# CTR_Power_Supply.net
KiCad netlist of a schematic drawn in Altium Designer
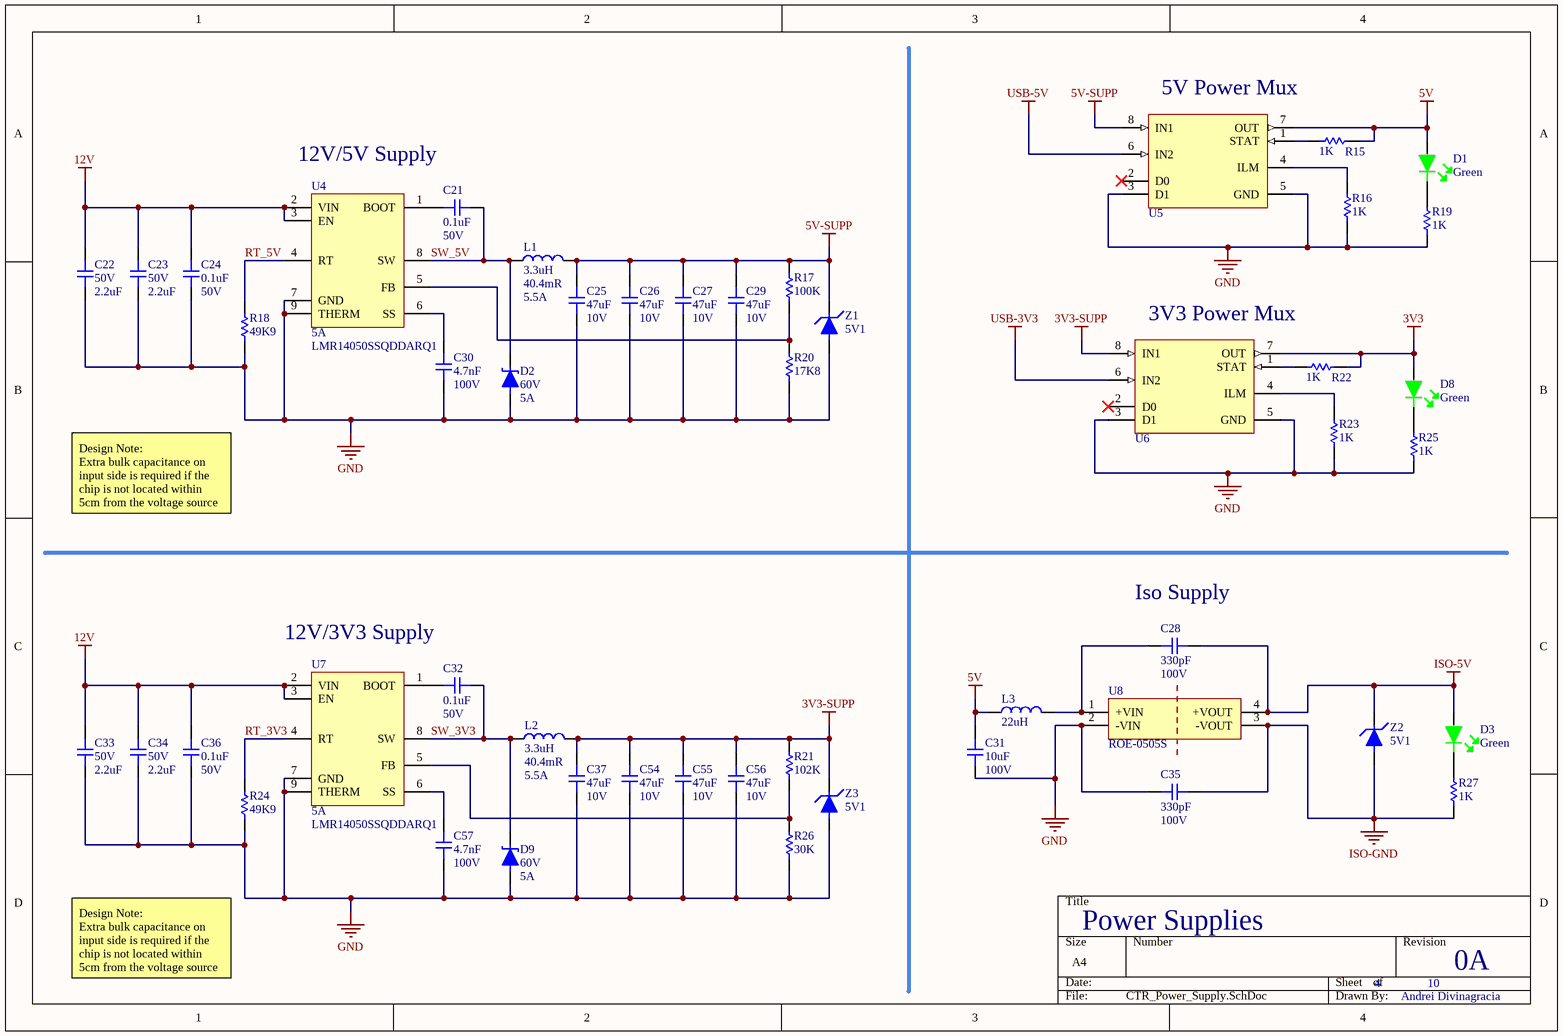
[diagram p0: CTR_Power_Supply.SchDoc]

(export (version "E")
  (design (tool "Eeschema 10.0.6"))
  (components
    (comp (ref "C21")
      (value "0.1uF")
      (footprint "CAP-0603")
      (description "CAP CER 0.1UF 50V X7R 0603")
      (fields
        (field (name "MANUFACTURER") "Samsung")
        (field (name "MANUFACTURER PART NUMBER") "CL10B104KB8NNNL")
        (field (name "VOLTAGE RATING") "50V")
      )
      (libsource (lib "InverterSCHLib") (part "0603-0.1uF-50V"))
    )
    (comp (ref "C22")
      (value "0805-2.2uF-50V")
      (footprint "CAP-0805")
      (description "CAP CER 2.2UF 50V X5R 0805")
      (fields
        (field (name "MANUFACTURER") "Samsung")
        (field (name "MANUFACTURER PART NUMBER") "CL21A225KBFNNNE")
        (field (name "VOLTAGE RATING") "50V")
        (field (name "CAPACITANCE") "2.2uF")
      )
      (libsource (lib "InverterSCHLib") (part "0805-2.2uF-50V"))
    )
    (comp (ref "C23")
      (value "0805-2.2uF-50V")
      (footprint "CAP-0805")
      (description "CAP CER 2.2UF 50V X5R 0805")
      (fields
        (field (name "MANUFACTURER") "Samsung")
        (field (name "MANUFACTURER PART NUMBER") "CL21A225KBFNNNE")
        (field (name "VOLTAGE RATING") "50V")
        (field (name "CAPACITANCE") "2.2uF")
      )
      (libsource (lib "InverterSCHLib") (part "0805-2.2uF-50V"))
    )
    (comp (ref "C24")
      (value "0.1uF")
      (footprint "CAP-0603")
      (description "CAP CER 0.1UF 50V X7R 0603")
      (fields
        (field (name "MANUFACTURER") "Samsung")
        (field (name "MANUFACTURER PART NUMBER") "CL10B104KB8NNNL")
        (field (name "VOLTAGE RATING") "50V")
      )
      (libsource (lib "InverterSCHLib") (part "0603-0.1uF-50V"))
    )
    (comp (ref "C25")
      (value "47uF")
      (footprint "CAP-1206")
      (description "CAP CER 47UF 10V X5R 1206")
      (fields
        (field (name "MANUFACTURER") "Samsung")
        (field (name "MANUFACTURER PART NUMBER") "CL31A476MPHNNNE")
        (field (name "VOLTAGE RATING") "10V")
      )
      (libsource (lib "InverterSCHLib") (part "1206-47uF"))
    )
    (comp (ref "C26")
      (value "47uF")
      (footprint "CAP-1206")
      (description "CAP CER 47UF 10V X5R 1206")
      (fields
        (field (name "MANUFACTURER") "Samsung")
        (field (name "MANUFACTURER PART NUMBER") "CL31A476MPHNNNE")
        (field (name "VOLTAGE RATING") "10V")
      )
      (libsource (lib "InverterSCHLib") (part "1206-47uF"))
    )
    (comp (ref "C27")
      (value "47uF")
      (footprint "CAP-1206")
      (description "CAP CER 47UF 10V X5R 1206")
      (fields
        (field (name "MANUFACTURER") "Samsung")
        (field (name "MANUFACTURER PART NUMBER") "CL31A476MPHNNNE")
        (field (name "VOLTAGE RATING") "10V")
      )
      (libsource (lib "InverterSCHLib") (part "1206-47uF"))
    )
    (comp (ref "C28")
      (value "330pF")
      (footprint "CAP-0805")
      (description "CAP CER 330PF 100V X7R 0805")
      (fields
        (field (name "MANUFACTURER") "Wurth Electronics")
        (field (name "MANUFACTURER PART NUMBER") "885012207113")
        (field (name "VOLTAGE RATING") "100V")
      )
      (libsource (lib "InverterSCHLib") (part "0805-330pF-100V"))
    )
    (comp (ref "C29")
      (value "47uF")
      (footprint "CAP-1206")
      (description "CAP CER 47UF 10V X5R 1206")
      (fields
        (field (name "MANUFACTURER") "Samsung")
        (field (name "MANUFACTURER PART NUMBER") "CL31A476MPHNNNE")
        (field (name "VOLTAGE RATING") "10V")
      )
      (libsource (lib "InverterSCHLib") (part "1206-47uF"))
    )
    (comp (ref "C30")
      (value "4.7nF")
      (footprint "CAP-0603")
      (description "CAP CER 4700PF 100V X7R 0603")
      (fields
        (field (name "MANUFACTURER") "TDK")
        (field (name "MANUFACTURER PART NUMBER") "CGA3E2X7R2A472K080AA")
        (field (name "VOLTAGE RATING") "100V")
      )
      (libsource (lib "InverterSCHLib") (part "0603-4.7nF-100V"))
    )
    (comp (ref "C31")
      (value "10uF")
      (description "CAP CER 10UF 100V X7S 2220")
      (fields
        (field (name "MANUFACTURER") "TDK")
        (field (name "MANUFACTURER PART NUMBER") "C5750X7S2A106K230KB")
        (field (name "VOLTAGE RATING") "100V")
      )
      (libsource (lib "InverterSCHLib") (part "2220-10uF-100V"))
    )
    (comp (ref "C32")
      (value "0.1uF")
      (footprint "CAP-0603")
      (description "CAP CER 0.1UF 50V X7R 0603")
      (fields
        (field (name "MANUFACTURER") "Samsung")
        (field (name "MANUFACTURER PART NUMBER") "CL10B104KB8NNNL")
        (field (name "VOLTAGE RATING") "50V")
      )
      (libsource (lib "InverterSCHLib") (part "0603-0.1uF-50V"))
    )
    (comp (ref "C33")
      (value "0805-2.2uF-50V")
      (footprint "CAP-0805")
      (description "CAP CER 2.2UF 50V X5R 0805")
      (fields
        (field (name "MANUFACTURER") "Samsung")
        (field (name "MANUFACTURER PART NUMBER") "CL21A225KBFNNNE")
        (field (name "VOLTAGE RATING") "50V")
        (field (name "CAPACITANCE") "2.2uF")
      )
      (libsource (lib "InverterSCHLib") (part "0805-2.2uF-50V"))
    )
    (comp (ref "C34")
      (value "0805-2.2uF-50V")
      (footprint "CAP-0805")
      (description "CAP CER 2.2UF 50V X5R 0805")
      (fields
        (field (name "MANUFACTURER") "Samsung")
        (field (name "MANUFACTURER PART NUMBER") "CL21A225KBFNNNE")
        (field (name "VOLTAGE RATING") "50V")
        (field (name "CAPACITANCE") "2.2uF")
      )
      (libsource (lib "InverterSCHLib") (part "0805-2.2uF-50V"))
    )
    (comp (ref "C35")
      (value "330pF")
      (footprint "CAP-0805")
      (description "CAP CER 330PF 100V X7R 0805")
      (fields
        (field (name "MANUFACTURER") "Wurth Electronics")
        (field (name "MANUFACTURER PART NUMBER") "885012207113")
        (field (name "VOLTAGE RATING") "100V")
      )
      (libsource (lib "InverterSCHLib") (part "0805-330pF-100V"))
    )
    (comp (ref "C36")
      (value "0.1uF")
      (footprint "CAP-0603")
      (description "CAP CER 0.1UF 50V X7R 0603")
      (fields
        (field (name "MANUFACTURER") "Samsung")
        (field (name "MANUFACTURER PART NUMBER") "CL10B104KB8NNNL")
        (field (name "VOLTAGE RATING") "50V")
      )
      (libsource (lib "InverterSCHLib") (part "0603-0.1uF-50V"))
    )
    (comp (ref "C37")
      (value "47uF")
      (footprint "CAP-1206")
      (description "CAP CER 47UF 10V X5R 1206")
      (fields
        (field (name "MANUFACTURER") "Samsung")
        (field (name "MANUFACTURER PART NUMBER") "CL31A476MPHNNNE")
        (field (name "VOLTAGE RATING") "10V")
      )
      (libsource (lib "InverterSCHLib") (part "1206-47uF"))
    )
    (comp (ref "C54")
      (value "47uF")
      (footprint "CAP-1206")
      (description "CAP CER 47UF 10V X5R 1206")
      (fields
        (field (name "MANUFACTURER") "Samsung")
        (field (name "MANUFACTURER PART NUMBER") "CL31A476MPHNNNE")
        (field (name "VOLTAGE RATING") "10V")
      )
      (libsource (lib "InverterSCHLib") (part "1206-47uF"))
    )
    (comp (ref "C55")
      (value "47uF")
      (footprint "CAP-1206")
      (description "CAP CER 47UF 10V X5R 1206")
      (fields
        (field (name "MANUFACTURER") "Samsung")
        (field (name "MANUFACTURER PART NUMBER") "CL31A476MPHNNNE")
        (field (name "VOLTAGE RATING") "10V")
      )
      (libsource (lib "InverterSCHLib") (part "1206-47uF"))
    )
    (comp (ref "C56")
      (value "47uF")
      (footprint "CAP-1206")
      (description "CAP CER 47UF 10V X5R 1206")
      (fields
        (field (name "MANUFACTURER") "Samsung")
        (field (name "MANUFACTURER PART NUMBER") "CL31A476MPHNNNE")
        (field (name "VOLTAGE RATING") "10V")
      )
      (libsource (lib "InverterSCHLib") (part "1206-47uF"))
    )
    (comp (ref "C57")
      (value "4.7nF")
      (footprint "CAP-0603")
      (description "CAP CER 4700PF 100V X7R 0603")
      (fields
        (field (name "MANUFACTURER") "TDK")
        (field (name "MANUFACTURER PART NUMBER") "CGA3E2X7R2A472K080AA")
        (field (name "VOLTAGE RATING") "100V")
      )
      (libsource (lib "InverterSCHLib") (part "0603-4.7nF-100V"))
    )
    (comp (ref "D1")
      (value "Green")
      (footprint "LED-0603")
      (description "LED GREEN CLEAR 0603 SMD")
      (fields
        (field (name "MANUFACTURER") "Wurth Electronics")
        (field (name "MANUFACTURER PART NUMBER") "150060VS75000")
      )
      (libsource (lib "InverterSCHLib") (part "LED-Green"))
    )
    (comp (ref "D2")
      (value "B560C-13-F")
      (footprint "DO-214AB, SMC")
      (description "DIODE SCHOTTKY 60V 5A SMC")
      (fields
        (field (name "MANUFACTURER") "Diodes")
        (field (name "VOLTAGE RATING (DC)") "60V")
        (field (name "CURRENT RATING") "5A")
      )
      (libsource (lib "InverterSCHLib") (part "B560C-13-F"))
    )
    (comp (ref "D3")
      (value "Green")
      (footprint "LED-0603")
      (description "LED GREEN CLEAR 0603 SMD")
      (fields
        (field (name "MANUFACTURER") "Wurth Electronics")
        (field (name "MANUFACTURER PART NUMBER") "150060VS75000")
      )
      (libsource (lib "InverterSCHLib") (part "LED-Green"))
    )
    (comp (ref "D8")
      (value "Green")
      (footprint "LED-0603")
      (description "LED GREEN CLEAR 0603 SMD")
      (fields
        (field (name "MANUFACTURER") "Wurth Electronics")
        (field (name "MANUFACTURER PART NUMBER") "150060VS75000")
      )
      (libsource (lib "InverterSCHLib") (part "LED-Green"))
    )
    (comp (ref "D9")
      (value "B560C-13-F")
      (footprint "DO-214AB, SMC")
      (description "DIODE SCHOTTKY 60V 5A SMC")
      (fields
        (field (name "MANUFACTURER") "Diodes")
        (field (name "VOLTAGE RATING (DC)") "60V")
        (field (name "CURRENT RATING") "5A")
      )
      (libsource (lib "InverterSCHLib") (part "B560C-13-F"))
    )
    (comp (ref "L1")
      (value "IND-3.3uH-5.5A")
      (footprint "INDM5252X30N")
      (description "FIXED IND 3.3UH 5.5A 40.4MOHM SM")
      (fields
        (field (name "MANUFACTURER") "Vishay Dale")
        (field (name "MANUFACTURER PART NUMBER") "IHLP2020CZER3R3M11")
        (field (name "INDUCTANCE") "3.3uH")
        (field (name "DC RESISTANCE (DCR)") "40.4mR")
        (field (name "CURRENT RATING") "5.5A")
      )
      (libsource (lib "InverterSCHLib") (part "IND-3.3uH-5.5A"))
    )
    (comp (ref "L2")
      (value "IND-3.3uH-5.5A")
      (footprint "INDM5252X30N")
      (description "FIXED IND 3.3UH 5.5A 40.4MOHM SM")
      (fields
        (field (name "MANUFACTURER") "Vishay Dale")
        (field (name "MANUFACTURER PART NUMBER") "IHLP2020CZER3R3M11")
        (field (name "INDUCTANCE") "3.3uH")
        (field (name "DC RESISTANCE (DCR)") "40.4mR")
        (field (name "CURRENT RATING") "5.5A")
      )
      (libsource (lib "InverterSCHLib") (part "IND-3.3uH-5.5A"))
    )
    (comp (ref "L3")
      (value "22uH")
      (footprint "IND-4532")
      (description "FIXED IND 22UH 630MA 700MOHM SMD")
      (fields (field (name "MANUFACTURER") "Recom") (field (name "MANUFACTURER PART NUMBER") "RLS-226"))
      (libsource (lib "InverterSCHLib") (part "IND-22uH-630mA"))
    )
    (comp (ref "R15")
      (value "1K")
      (footprint "RES-0603")
      (description "RES SMD 1K OHM 1% 1/10W 0603")
      (fields
        (field (name "MANUFACTURER") "Vishay Dale")
        (field (name "MANUFACTURER PART NUMBER") "CRCW06031K00FKEA")
      )
      (libsource (lib "InverterSCHLib") (part "0603-1KR"))
    )
    (comp (ref "R16")
      (value "1K")
      (footprint "RES-0603")
      (description "RES SMD 1K OHM 1% 1/10W 0603")
      (fields
        (field (name "MANUFACTURER") "Vishay Dale")
        (field (name "MANUFACTURER PART NUMBER") "CRCW06031K00FKEA")
      )
      (libsource (lib "InverterSCHLib") (part "0603-1KR"))
    )
    (comp (ref "R17")
      (value "100K")
      (description "RES SMD 100K OHM 1% 1/10W 0603")
      (fields
        (field (name "MANUFACTURER") "Yageo")
        (field (name "MANUFACTURER PART NUMBER") "RC0603FR-07100KL")
      )
      (libsource (lib "InverterSCHLib") (part "0603-100K"))
    )
    (comp (ref "R18")
      (value "49K9")
      (footprint "RES-0603")
      (description "RES SMD 49.9KOHM 0.5% 1/10W 0603")
      (fields
        (field (name "MANUFACTURER") "Vishay Dale")
        (field (name "MANUFACTURER PART NUMBER") "CRCW060349K9DHEAP")
      )
      (libsource (lib "InverterSCHLib") (part "0603-49K9"))
    )
    (comp (ref "R19")
      (value "1K")
      (footprint "RES-0603")
      (description "RES SMD 1K OHM 1% 1/10W 0603")
      (fields
        (field (name "MANUFACTURER") "Vishay Dale")
        (field (name "MANUFACTURER PART NUMBER") "CRCW06031K00FKEA")
      )
      (libsource (lib "InverterSCHLib") (part "0603-1KR"))
    )
    (comp (ref "R20")
      (value "17K8")
      (footprint "RES-0603")
      (description "RES SMD 17.8K OHM 1% 1/10W 0603")
      (fields
        (field (name "MANUFACTURER") "Yageo")
        (field (name "MANUFACTURER PART NUMBER") "RC0603FR-0717K8L")
      )
      (libsource (lib "InverterSCHLib") (part "0603-17K8"))
    )
    (comp (ref "R21")
      (value "102K")
      (footprint "RES-0603")
      (description "RES SMD 102K OHM 1% 1/10W 0603")
      (fields
        (field (name "MANUFACTURER") "Samsung")
        (field (name "MANUFACTURER PART NUMBER") "RC1608F1023CS")
      )
      (libsource (lib "InverterSCHLib") (part "0603-102K"))
    )
    (comp (ref "R22")
      (value "1K")
      (footprint "RES-0603")
      (description "RES SMD 1K OHM 1% 1/10W 0603")
      (fields
        (field (name "MANUFACTURER") "Vishay Dale")
        (field (name "MANUFACTURER PART NUMBER") "CRCW06031K00FKEA")
      )
      (libsource (lib "InverterSCHLib") (part "0603-1KR"))
    )
    (comp (ref "R23")
      (value "1K")
      (footprint "RES-0603")
      (description "RES SMD 1K OHM 1% 1/10W 0603")
      (fields
        (field (name "MANUFACTURER") "Vishay Dale")
        (field (name "MANUFACTURER PART NUMBER") "CRCW06031K00FKEA")
      )
      (libsource (lib "InverterSCHLib") (part "0603-1KR"))
    )
    (comp (ref "R24")
      (value "49K9")
      (footprint "RES-0603")
      (description "RES SMD 49.9KOHM 0.5% 1/10W 0603")
      (fields
        (field (name "MANUFACTURER") "Vishay Dale")
        (field (name "MANUFACTURER PART NUMBER") "CRCW060349K9DHEAP")
      )
      (libsource (lib "InverterSCHLib") (part "0603-49K9"))
    )
    (comp (ref "R25")
      (value "1K")
      (footprint "RES-0603")
      (description "RES SMD 1K OHM 1% 1/10W 0603")
      (fields
        (field (name "MANUFACTURER") "Vishay Dale")
        (field (name "MANUFACTURER PART NUMBER") "CRCW06031K00FKEA")
      )
      (libsource (lib "InverterSCHLib") (part "0603-1KR"))
    )
    (comp (ref "R26")
      (value "30K")
      (footprint "RES-0603")
      (description "RES SMD 30K OHM 1% 1/10W 0603")
      (fields
        (field (name "MANUFACTURER") "Yageo")
        (field (name "MANUFACTURER PART NUMBER") "RC0603FR-0730KL")
      )
      (libsource (lib "InverterSCHLib") (part "0603-30KR"))
    )
    (comp (ref "R27")
      (value "1K")
      (footprint "RES-0603")
      (description "RES SMD 1K OHM 1% 1/10W 0603")
      (fields
        (field (name "MANUFACTURER") "Vishay Dale")
        (field (name "MANUFACTURER PART NUMBER") "CRCW06031K00FKEA")
      )
      (libsource (lib "InverterSCHLib") (part "0603-1KR"))
    )
    (comp (ref "U4")
      (value "LMR14050SSQDDARQ1")
      (footprint "8-SOIC W THRM")
      (description "IC REG BUCK ADJUSTABLE 5A 8SOPWR")
      (fields
        (field (name "MANUFACTURER") "Texas Instruments")
        (field (name "OUTPUT CURRENT") "5A")
        (field (name "MANUFACTURER PART NUMBER") "LMR14050SSQDDARQ1")
      )
      (libsource (lib "InverterSCHLib") (part "LMR14050SSQDDARQ1"))
    )
    (comp (ref "U5")
      (value "TPS2115APWR")
      (footprint "8-TSSOP-POW-SW")
      (description "IC OR CTRLR SRC SELECT 8TSSOP")
      (fields (field (name "MANUFACTURER") "Texas Instruments"))
      (libsource (lib "InverterSCHLib") (part "TPS2115APWR"))
    )
    (comp (ref "U6")
      (value "TPS2115APWR")
      (footprint "8-TSSOP-POW-SW")
      (description "IC OR CTRLR SRC SELECT 8TSSOP")
      (fields (field (name "MANUFACTURER") "Texas Instruments"))
      (libsource (lib "InverterSCHLib") (part "TPS2115APWR"))
    )
    (comp (ref "U7")
      (value "LMR14050SSQDDARQ1")
      (footprint "8-SOIC W THRM")
      (description "IC REG BUCK ADJUSTABLE 5A 8SOPWR")
      (fields
        (field (name "MANUFACTURER") "Texas Instruments")
        (field (name "OUTPUT CURRENT") "5A")
        (field (name "MANUFACTURER PART NUMBER") "LMR14050SSQDDARQ1")
      )
      (libsource (lib "InverterSCHLib") (part "LMR14050SSQDDARQ1"))
    )
    (comp (ref "U8")
      (value "ROE-0505S")
      (footprint "ROE-0505S")
      (description "Module DC-DC 5VIN 1-OUT 5V 0.2A 1W 4-Pin SIP Tube")
      (fields (field (name "MANUFACTURER") "Recom") (field (name "MANUFACTURER PART NUMBER") "ROE-0505S"))
      (libsource (lib "InverterSCHLib") (part "ROE-0505S"))
    )
    (comp (ref "Z1")
      (value "5V1")
      (footprint "SOD-123")
      (description "DIODE ZENER 5.1V 500MW SOD123")
      (fields
        (field (name "MANUFACTURER") "ON Semiconductor")
        (field (name "MANUFACTURER PART NUMBER") "SZMMSZ4689T1G")
      )
      (libsource (lib "InverterSCHLib") (part "SZMMSZ4689T1G"))
    )
    (comp (ref "Z2")
      (value "5V1")
      (footprint "SOD-123")
      (description "DIODE ZENER 5.1V 500MW SOD123")
      (fields
        (field (name "MANUFACTURER") "ON Semiconductor")
        (field (name "MANUFACTURER PART NUMBER") "SZMMSZ4689T1G")
      )
      (libsource (lib "InverterSCHLib") (part "SZMMSZ4689T1G"))
    )
    (comp (ref "Z3")
      (value "5V1")
      (footprint "SOD-123")
      (description "DIODE ZENER 5.1V 500MW SOD123")
      (fields
        (field (name "MANUFACTURER") "ON Semiconductor")
        (field (name "MANUFACTURER PART NUMBER") "SZMMSZ4689T1G")
      )
      (libsource (lib "InverterSCHLib") (part "SZMMSZ4689T1G"))
    )
  )
  (nets
    (net (code "1") (name "/RT_3V3") (class "Default")
      (node (ref "R24") (pin "2") (pinfunction "2_2") (pintype "passive"))
      (node (ref "U7") (pin "4") (pinfunction "RT_4") (pintype "passive"))
    )
    (net (code "2") (name "/RT_5V") (class "Default")
      (node (ref "R18") (pin "2") (pinfunction "2_2") (pintype "passive"))
      (node (ref "U4") (pin "4") (pinfunction "RT_4") (pintype "passive"))
    )
    (net (code "3") (name "/SW_3V3") (class "Default")
      (node (ref "C32") (pin "1") (pinfunction "1_1") (pintype "passive"))
      (node (ref "D9") (pin "1") (pinfunction "1_1") (pintype "passive"))
      (node (ref "L2") (pin "1") (pinfunction "1_1") (pintype "passive"))
      (node (ref "U7") (pin "8") (pinfunction "SW_8") (pintype "passive"))
    )
    (net (code "4") (name "/SW_5V") (class "Default")
      (node (ref "C21") (pin "1") (pinfunction "1_1") (pintype "passive"))
      (node (ref "D2") (pin "1") (pinfunction "1_1") (pintype "passive"))
      (node (ref "L1") (pin "1") (pinfunction "1_1") (pintype "passive"))
      (node (ref "U4") (pin "8") (pinfunction "SW_8") (pintype "passive"))
    )
    (net (code "5") (name "3V3") (class "Default")
      (node (ref "D8") (pin "1") (pinfunction "1_1") (pintype "passive"))
      (node (ref "R22") (pin "2") (pinfunction "2_2") (pintype "passive"))
      (node (ref "U6") (pin "7") (pinfunction "OUT_7") (pintype "output"))
    )
    (net (code "6") (name "3V3-SUPP") (class "Default")
      (node (ref "C37") (pin "2") (pinfunction "2_2") (pintype "passive"))
      (node (ref "C54") (pin "2") (pinfunction "2_2") (pintype "passive"))
      (node (ref "C55") (pin "2") (pinfunction "2_2") (pintype "passive"))
      (node (ref "C56") (pin "2") (pinfunction "2_2") (pintype "passive"))
      (node (ref "L2") (pin "2") (pinfunction "2_2") (pintype "passive"))
      (node (ref "R21") (pin "2") (pinfunction "2_2") (pintype "passive"))
      (node (ref "U6") (pin "8") (pinfunction "IN1_8") (pintype "input"))
      (node (ref "Z3") (pin "1") (pinfunction "1_1") (pintype "passive"))
    )
    (net (code "7") (name "5V") (class "Default")
      (node (ref "C31") (pin "2") (pinfunction "2_2") (pintype "passive"))
      (node (ref "D1") (pin "1") (pinfunction "1_1") (pintype "passive"))
      (node (ref "L3") (pin "1") (pinfunction "1_1") (pintype "passive"))
      (node (ref "R15") (pin "2") (pinfunction "2_2") (pintype "passive"))
      (node (ref "U5") (pin "7") (pinfunction "OUT_7") (pintype "output"))
    )
    (net (code "8") (name "5V-SUPP") (class "Default")
      (node (ref "C25") (pin "2") (pinfunction "2_2") (pintype "passive"))
      (node (ref "C26") (pin "2") (pinfunction "2_2") (pintype "passive"))
      (node (ref "C27") (pin "2") (pinfunction "2_2") (pintype "passive"))
      (node (ref "C29") (pin "2") (pinfunction "2_2") (pintype "passive"))
      (node (ref "L1") (pin "2") (pinfunction "2_2") (pintype "passive"))
      (node (ref "R17") (pin "1") (pinfunction "1_1") (pintype "passive"))
      (node (ref "U5") (pin "8") (pinfunction "IN1_8") (pintype "input"))
      (node (ref "Z1") (pin "1") (pinfunction "1_1") (pintype "passive"))
    )
    (net (code "9") (name "12V") (class "Default")
      (node (ref "C22") (pin "1") (pinfunction "1_1") (pintype "passive"))
      (node (ref "C23") (pin "1") (pinfunction "1_1") (pintype "passive"))
      (node (ref "C24") (pin "2") (pinfunction "2_2") (pintype "passive"))
      (node (ref "C33") (pin "1") (pinfunction "1_1") (pintype "passive"))
      (node (ref "C34") (pin "1") (pinfunction "1_1") (pintype "passive"))
      (node (ref "C36") (pin "2") (pinfunction "2_2") (pintype "passive"))
      (node (ref "U4") (pin "2") (pinfunction "VIN_2") (pintype "passive"))
      (node (ref "U4") (pin "3") (pinfunction "EN_3") (pintype "passive"))
      (node (ref "U7") (pin "2") (pinfunction "VIN_2") (pintype "passive"))
      (node (ref "U7") (pin "3") (pinfunction "EN_3") (pintype "passive"))
    )
    (net (code "10") (name "GND") (class "Default")
      (node (ref "C22") (pin "2") (pinfunction "2_2") (pintype "passive"))
      (node (ref "C23") (pin "2") (pinfunction "2_2") (pintype "passive"))
      (node (ref "C24") (pin "1") (pinfunction "1_1") (pintype "passive"))
      (node (ref "C25") (pin "1") (pinfunction "1_1") (pintype "passive"))
      (node (ref "C26") (pin "1") (pinfunction "1_1") (pintype "passive"))
      (node (ref "C27") (pin "1") (pinfunction "1_1") (pintype "passive"))
      (node (ref "C29") (pin "1") (pinfunction "1_1") (pintype "passive"))
      (node (ref "C30") (pin "1") (pinfunction "1_1") (pintype "passive"))
      (node (ref "C31") (pin "1") (pinfunction "1_1") (pintype "passive"))
      (node (ref "C33") (pin "2") (pinfunction "2_2") (pintype "passive"))
      (node (ref "C34") (pin "2") (pinfunction "2_2") (pintype "passive"))
      (node (ref "C35") (pin "1") (pinfunction "1_1") (pintype "passive"))
      (node (ref "C36") (pin "1") (pinfunction "1_1") (pintype "passive"))
      (node (ref "C37") (pin "1") (pinfunction "1_1") (pintype "passive"))
      (node (ref "C54") (pin "1") (pinfunction "1_1") (pintype "passive"))
      (node (ref "C55") (pin "1") (pinfunction "1_1") (pintype "passive"))
      (node (ref "C56") (pin "1") (pinfunction "1_1") (pintype "passive"))
      (node (ref "C57") (pin "1") (pinfunction "1_1") (pintype "passive"))
      (node (ref "D2") (pin "2") (pinfunction "2_2") (pintype "passive"))
      (node (ref "D9") (pin "2") (pinfunction "2_2") (pintype "passive"))
      (node (ref "R16") (pin "1") (pinfunction "1_1") (pintype "passive"))
      (node (ref "R18") (pin "1") (pinfunction "1_1") (pintype "passive"))
      (node (ref "R19") (pin "1") (pinfunction "1_1") (pintype "passive"))
      (node (ref "R20") (pin "1") (pinfunction "1_1") (pintype "passive"))
      (node (ref "R23") (pin "1") (pinfunction "1_1") (pintype "passive"))
      (node (ref "R24") (pin "1") (pinfunction "1_1") (pintype "passive"))
      (node (ref "R25") (pin "1") (pinfunction "1_1") (pintype "passive"))
      (node (ref "R26") (pin "1") (pinfunction "1_1") (pintype "passive"))
      (node (ref "U4") (pin "7") (pinfunction "GND_7") (pintype "passive"))
      (node (ref "U4") (pin "9") (pinfunction "THERM_9") (pintype "passive"))
      (node (ref "U5") (pin "3") (pinfunction "D1_3") (pintype "passive"))
      (node (ref "U5") (pin "5") (pinfunction "GND_5") (pintype "passive"))
      (node (ref "U6") (pin "3") (pinfunction "D1_3") (pintype "passive"))
      (node (ref "U6") (pin "5") (pinfunction "GND_5") (pintype "passive"))
      (node (ref "U7") (pin "7") (pinfunction "GND_7") (pintype "passive"))
      (node (ref "U7") (pin "9") (pinfunction "THERM_9") (pintype "passive"))
      (node (ref "U8") (pin "2") (pinfunction "-VIN_2") (pintype "passive"))
      (node (ref "Z1") (pin "2") (pinfunction "2_2") (pintype "passive"))
      (node (ref "Z3") (pin "2") (pinfunction "2_2") (pintype "passive"))
    )
    (net (code "11") (name "ISO-5V") (class "Default")
      (node (ref "C28") (pin "2") (pinfunction "2_2") (pintype "passive"))
      (node (ref "D3") (pin "1") (pinfunction "1_1") (pintype "passive"))
      (node (ref "U8") (pin "4") (pinfunction "+VOUT_4") (pintype "passive"))
      (node (ref "Z2") (pin "1") (pinfunction "1_1") (pintype "passive"))
    )
    (net (code "12") (name "ISO-GND") (class "Default")
      (node (ref "C35") (pin "2") (pinfunction "2_2") (pintype "passive"))
      (node (ref "R27") (pin "1") (pinfunction "1_1") (pintype "passive"))
      (node (ref "U8") (pin "3") (pinfunction "-VOUT_3") (pintype "passive"))
      (node (ref "Z2") (pin "2") (pinfunction "2_2") (pintype "passive"))
    )
    (net (code "13") (name "Net-(D1-Pad2)") (class "Default")
      (node (ref "D1") (pin "2") (pinfunction "2_2") (pintype "passive"))
      (node (ref "R19") (pin "2") (pinfunction "2_2") (pintype "passive"))
    )
    (net (code "14") (name "Net-(D3-Pad2)") (class "Default")
      (node (ref "D3") (pin "2") (pinfunction "2_2") (pintype "passive"))
      (node (ref "R27") (pin "2") (pinfunction "2_2") (pintype "passive"))
    )
    (net (code "15") (name "Net-(D8-Pad2)") (class "Default")
      (node (ref "D8") (pin "2") (pinfunction "2_2") (pintype "passive"))
      (node (ref "R25") (pin "2") (pinfunction "2_2") (pintype "passive"))
    )
    (net (code "16") (name "Net-(U4-BOOT)") (class "Default")
      (node (ref "C21") (pin "2") (pinfunction "2_2") (pintype "passive"))
      (node (ref "U4") (pin "1") (pinfunction "BOOT_1") (pintype "passive"))
    )
    (net (code "17") (name "Net-(U4-FB)") (class "Default")
      (node (ref "R17") (pin "2") (pinfunction "2_2") (pintype "passive"))
      (node (ref "R20") (pin "2") (pinfunction "2_2") (pintype "passive"))
      (node (ref "U4") (pin "5") (pinfunction "FB_5") (pintype "passive"))
    )
    (net (code "18") (name "Net-(U4-SS)") (class "Default")
      (node (ref "C30") (pin "2") (pinfunction "2_2") (pintype "passive"))
      (node (ref "U4") (pin "6") (pinfunction "SS_6") (pintype "passive"))
    )
    (net (code "19") (name "Net-(U5-ILM)") (class "Default")
      (node (ref "R16") (pin "2") (pinfunction "2_2") (pintype "passive"))
      (node (ref "U5") (pin "4") (pinfunction "ILM_4") (pintype "passive"))
    )
    (net (code "20") (name "Net-(U5-STAT)") (class "Default")
      (node (ref "R15") (pin "1") (pinfunction "1_1") (pintype "passive"))
      (node (ref "U5") (pin "1") (pinfunction "STAT_1") (pintype "input"))
    )
    (net (code "21") (name "Net-(U6-ILM)") (class "Default")
      (node (ref "R23") (pin "2") (pinfunction "2_2") (pintype "passive"))
      (node (ref "U6") (pin "4") (pinfunction "ILM_4") (pintype "passive"))
    )
    (net (code "22") (name "Net-(U6-STAT)") (class "Default")
      (node (ref "R22") (pin "1") (pinfunction "1_1") (pintype "passive"))
      (node (ref "U6") (pin "1") (pinfunction "STAT_1") (pintype "input"))
    )
    (net (code "23") (name "Net-(U7-BOOT)") (class "Default")
      (node (ref "C32") (pin "2") (pinfunction "2_2") (pintype "passive"))
      (node (ref "U7") (pin "1") (pinfunction "BOOT_1") (pintype "passive"))
    )
    (net (code "24") (name "Net-(U7-FB)") (class "Default")
      (node (ref "R21") (pin "1") (pinfunction "1_1") (pintype "passive"))
      (node (ref "R26") (pin "2") (pinfunction "2_2") (pintype "passive"))
      (node (ref "U7") (pin "5") (pinfunction "FB_5") (pintype "passive"))
    )
    (net (code "25") (name "Net-(U7-SS)") (class "Default")
      (node (ref "C57") (pin "2") (pinfunction "2_2") (pintype "passive"))
      (node (ref "U7") (pin "6") (pinfunction "SS_6") (pintype "passive"))
    )
    (net (code "26") (name "Net-(U8-+VIN)") (class "Default")
      (node (ref "C28") (pin "1") (pinfunction "1_1") (pintype "passive"))
      (node (ref "L3") (pin "2") (pinfunction "2_2") (pintype "passive"))
      (node (ref "U8") (pin "1") (pinfunction "+VIN_1") (pintype "passive"))
    )
    (net (code "27") (name "USB-3V3") (class "Default")
      (node (ref "U6") (pin "6") (pinfunction "IN2_6") (pintype "input"))
    )
    (net (code "28") (name "USB-5V") (class "Default")
      (node (ref "U5") (pin "6") (pinfunction "IN2_6") (pintype "input"))
    )
    (net (code "29") (name "unconnected-(U5-D0-Pad2)") (class "Default")
      (node (ref "U5") (pin "2") (pinfunction "D0_2") (pintype "passive+no_connect"))
    )
    (net (code "30") (name "unconnected-(U6-D0-Pad2)") (class "Default")
      (node (ref "U6") (pin "2") (pinfunction "D0_2") (pintype "passive+no_connect"))
    )
  )
)
